# Keyboard_CN.net
KiCad netlist of a schematic drawn in Altium Designer
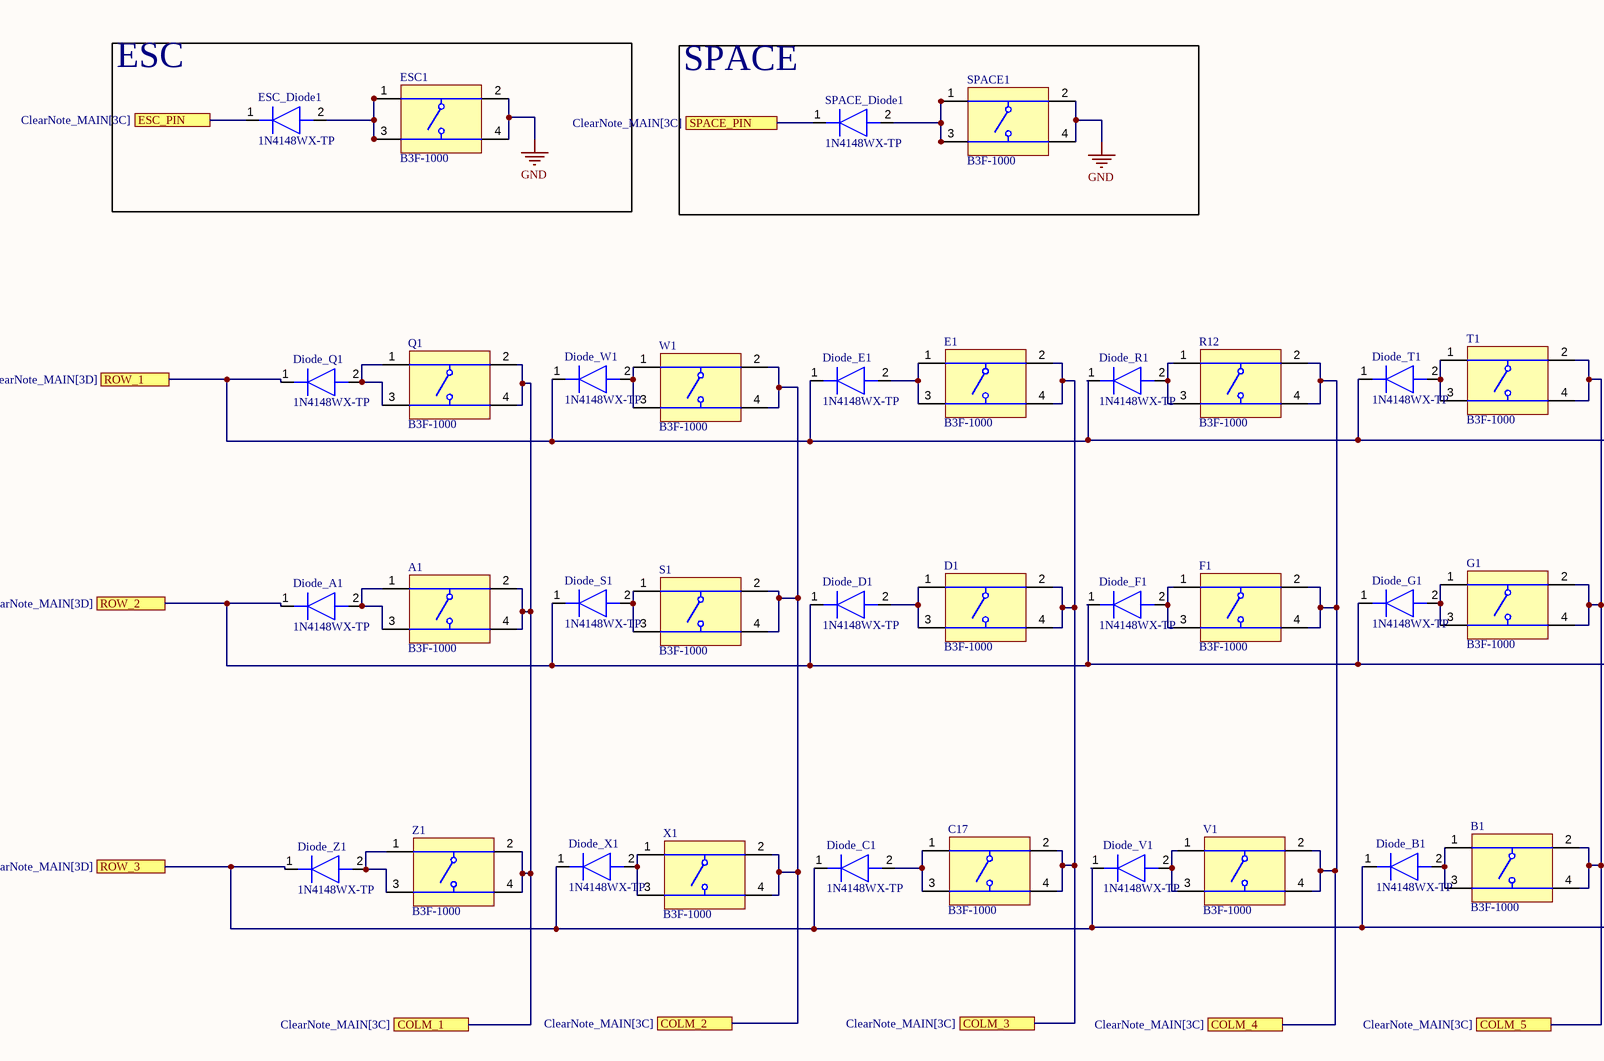
[diagram p0: Keyboard_CN.SchDoc, left]
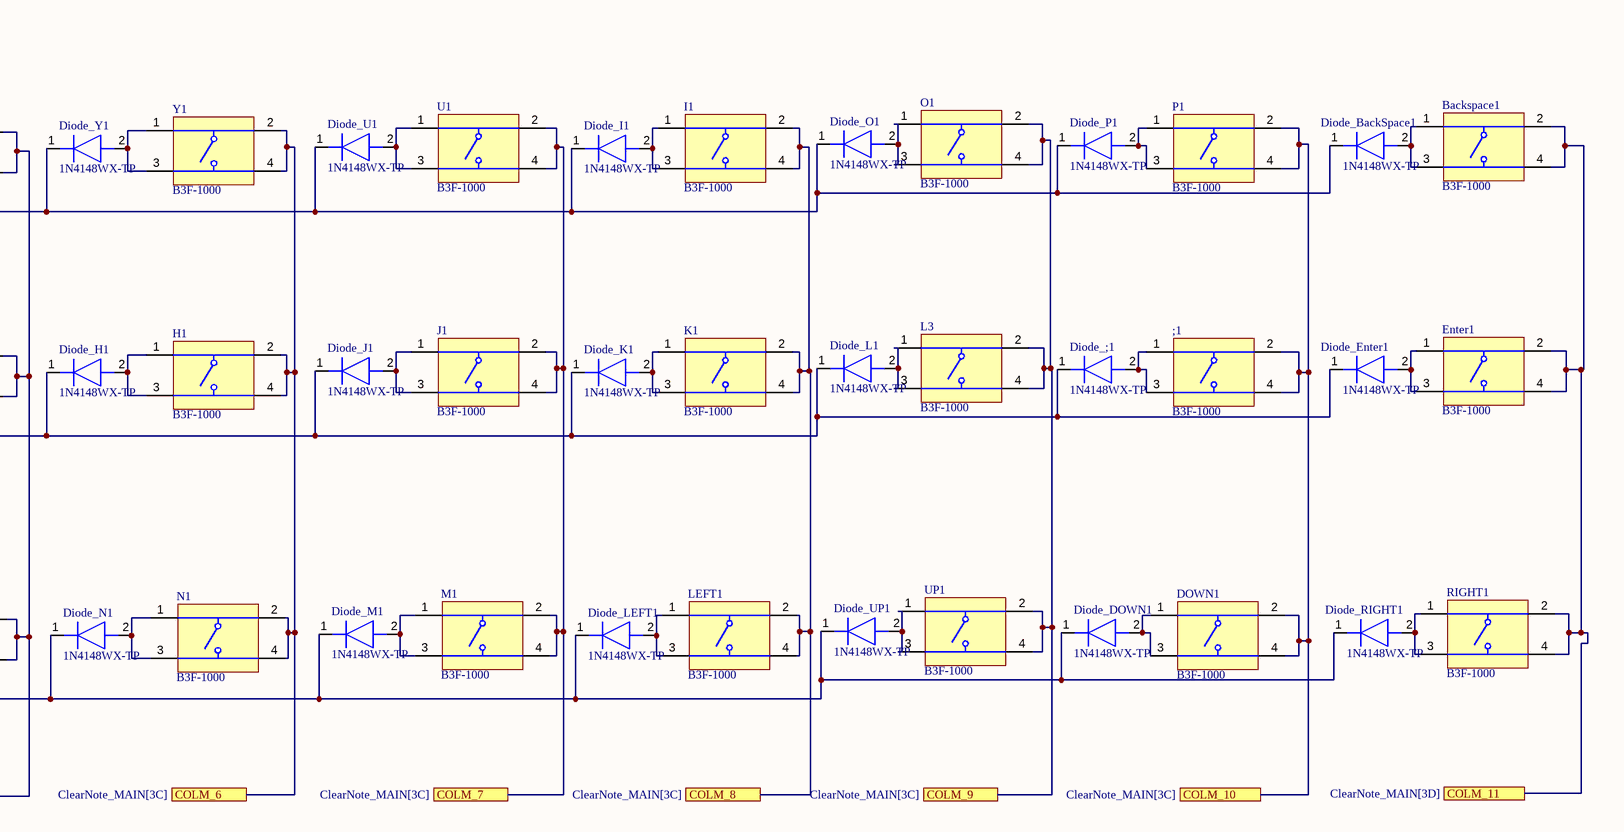
[diagram p1: Keyboard_CN.SchDoc, right]

(export (version "E")
  (design (tool "Eeschema 10.0.6"))
  (components
    (comp (ref ";1")
      (value "B3F-1000")
      (footprint "OMRON-B3F-1000-4_V")
      (description "Tactile Switch, SPST-NO, 0.05 A, 24 V, -25 to 70 degC, 4-Pin THD, RoHS, Bulk")
      (fields (field (name "MANUFACTURER") "Omron Electronic Components"))
      (libsource (lib "CAN") (part "SW-SPST-4_A"))
    )
    (comp (ref "A1")
      (value "B3F-1000")
      (footprint "OMRON-B3F-1000-4_V")
      (description "Tactile Switch, SPST-NO, 0.05 A, 24 V, -25 to 70 degC, 4-Pin THD, RoHS, Bulk")
      (fields (field (name "MANUFACTURER") "Omron Electronic Components"))
      (libsource (lib "CAN") (part "SW-SPST-4_A"))
    )
    (comp (ref "B1")
      (value "B3F-1000")
      (footprint "OMRON-B3F-1000-4_V")
      (description "Tactile Switch, SPST-NO, 0.05 A, 24 V, -25 to 70 degC, 4-Pin THD, RoHS, Bulk")
      (fields (field (name "MANUFACTURER") "Omron Electronic Components"))
      (libsource (lib "CAN") (part "SW-SPST-4_A"))
    )
    (comp (ref "Backspace1")
      (value "B3F-1000")
      (footprint "OMRON-B3F-1000-4_V")
      (description "Tactile Switch, SPST-NO, 0.05 A, 24 V, -25 to 70 degC, 4-Pin THD, RoHS, Bulk")
      (fields (field (name "MANUFACTURER") "Omron Electronic Components"))
      (libsource (lib "CAN") (part "SW-SPST-4_A"))
    )
    (comp (ref "C17")
      (value "B3F-1000")
      (footprint "OMRON-B3F-1000-4_V")
      (description "Tactile Switch, SPST-NO, 0.05 A, 24 V, -25 to 70 degC, 4-Pin THD, RoHS, Bulk")
      (fields (field (name "MANUFACTURER") "Omron Electronic Components"))
      (libsource (lib "CAN") (part "SW-SPST-4_A"))
    )
    (comp (ref "D1")
      (value "B3F-1000")
      (footprint "OMRON-B3F-1000-4_V")
      (description "Tactile Switch, SPST-NO, 0.05 A, 24 V, -25 to 70 degC, 4-Pin THD, RoHS, Bulk")
      (fields (field (name "MANUFACTURER") "Omron Electronic Components"))
      (libsource (lib "CAN") (part "SW-SPST-4_A"))
    )
    (comp (ref "Diode_;1")
      (value "1N4148WX-TP")
      (footprint "SamacSys:SOD2512X130N")
      (description "Diode")
      (libsource (lib "*") (part "1N4148WX-TP"))
    )
    (comp (ref "Diode_A1")
      (value "1N4148WX-TP")
      (footprint "SamacSys:SOD2512X130N")
      (description "Diode")
      (libsource (lib "*") (part "1N4148WX-TP"))
    )
    (comp (ref "Diode_B1")
      (value "1N4148WX-TP")
      (footprint "SamacSys:SOD2512X130N")
      (description "Diode")
      (libsource (lib "*") (part "1N4148WX-TP"))
    )
    (comp (ref "Diode_BackSpace1")
      (value "1N4148WX-TP")
      (footprint "SamacSys:SOD2512X130N")
      (description "Diode")
      (libsource (lib "*") (part "1N4148WX-TP"))
    )
    (comp (ref "Diode_C1")
      (value "1N4148WX-TP")
      (footprint "SamacSys:SOD2512X130N")
      (description "Diode")
      (libsource (lib "*") (part "1N4148WX-TP"))
    )
    (comp (ref "Diode_D1")
      (value "1N4148WX-TP")
      (footprint "SamacSys:SOD2512X130N")
      (description "Diode")
      (libsource (lib "*") (part "1N4148WX-TP"))
    )
    (comp (ref "Diode_DOWN1")
      (value "1N4148WX-TP")
      (footprint "SamacSys:SOD2512X130N")
      (description "Diode")
      (libsource (lib "*") (part "1N4148WX-TP"))
    )
    (comp (ref "Diode_E1")
      (value "1N4148WX-TP")
      (footprint "SamacSys:SOD2512X130N")
      (description "Diode")
      (libsource (lib "*") (part "1N4148WX-TP"))
    )
    (comp (ref "Diode_Enter1")
      (value "1N4148WX-TP")
      (footprint "SamacSys:SOD2512X130N")
      (description "Diode")
      (libsource (lib "*") (part "1N4148WX-TP"))
    )
    (comp (ref "Diode_F1")
      (value "1N4148WX-TP")
      (footprint "SamacSys:SOD2512X130N")
      (description "Diode")
      (libsource (lib "*") (part "1N4148WX-TP"))
    )
    (comp (ref "Diode_G1")
      (value "1N4148WX-TP")
      (footprint "SamacSys:SOD2512X130N")
      (description "Diode")
      (libsource (lib "*") (part "1N4148WX-TP"))
    )
    (comp (ref "Diode_H1")
      (value "1N4148WX-TP")
      (footprint "SamacSys:SOD2512X130N")
      (description "Diode")
      (libsource (lib "*") (part "1N4148WX-TP"))
    )
    (comp (ref "Diode_I1")
      (value "1N4148WX-TP")
      (footprint "SamacSys:SOD2512X130N")
      (description "Diode")
      (libsource (lib "*") (part "1N4148WX-TP"))
    )
    (comp (ref "Diode_J1")
      (value "1N4148WX-TP")
      (footprint "SamacSys:SOD2512X130N")
      (description "Diode")
      (libsource (lib "*") (part "1N4148WX-TP"))
    )
    (comp (ref "Diode_K1")
      (value "1N4148WX-TP")
      (footprint "SamacSys:SOD2512X130N")
      (description "Diode")
      (libsource (lib "*") (part "1N4148WX-TP"))
    )
    (comp (ref "Diode_L1")
      (value "1N4148WX-TP")
      (footprint "SamacSys:SOD2512X130N")
      (description "Diode")
      (libsource (lib "*") (part "1N4148WX-TP"))
    )
    (comp (ref "Diode_LEFT1")
      (value "1N4148WX-TP")
      (footprint "SamacSys:SOD2512X130N")
      (description "Diode")
      (libsource (lib "*") (part "1N4148WX-TP"))
    )
    (comp (ref "Diode_M1")
      (value "1N4148WX-TP")
      (footprint "SamacSys:SOD2512X130N")
      (description "Diode")
      (libsource (lib "*") (part "1N4148WX-TP"))
    )
    (comp (ref "Diode_N1")
      (value "1N4148WX-TP")
      (footprint "SamacSys:SOD2512X130N")
      (description "Diode")
      (libsource (lib "*") (part "1N4148WX-TP"))
    )
    (comp (ref "Diode_O1")
      (value "1N4148WX-TP")
      (footprint "SamacSys:SOD2512X130N")
      (description "Diode")
      (libsource (lib "*") (part "1N4148WX-TP"))
    )
    (comp (ref "Diode_P1")
      (value "1N4148WX-TP")
      (footprint "SamacSys:SOD2512X130N")
      (description "Diode")
      (libsource (lib "*") (part "1N4148WX-TP"))
    )
    (comp (ref "Diode_Q1")
      (value "1N4148WX-TP")
      (footprint "SamacSys:SOD2512X130N")
      (description "Diode")
      (libsource (lib "*") (part "1N4148WX-TP"))
    )
    (comp (ref "Diode_R1")
      (value "1N4148WX-TP")
      (footprint "SamacSys:SOD2512X130N")
      (description "Diode")
      (libsource (lib "*") (part "1N4148WX-TP"))
    )
    (comp (ref "Diode_RIGHT1")
      (value "1N4148WX-TP")
      (footprint "SamacSys:SOD2512X130N")
      (description "Diode")
      (libsource (lib "*") (part "1N4148WX-TP"))
    )
    (comp (ref "Diode_S1")
      (value "1N4148WX-TP")
      (footprint "SamacSys:SOD2512X130N")
      (description "Diode")
      (libsource (lib "*") (part "1N4148WX-TP"))
    )
    (comp (ref "Diode_T1")
      (value "1N4148WX-TP")
      (footprint "SamacSys:SOD2512X130N")
      (description "Diode")
      (libsource (lib "*") (part "1N4148WX-TP"))
    )
    (comp (ref "Diode_U1")
      (value "1N4148WX-TP")
      (footprint "SamacSys:SOD2512X130N")
      (description "Diode")
      (libsource (lib "*") (part "1N4148WX-TP"))
    )
    (comp (ref "Diode_UP1")
      (value "1N4148WX-TP")
      (footprint "SamacSys:SOD2512X130N")
      (description "Diode")
      (libsource (lib "*") (part "1N4148WX-TP"))
    )
    (comp (ref "Diode_V1")
      (value "1N4148WX-TP")
      (footprint "SamacSys:SOD2512X130N")
      (description "Diode")
      (libsource (lib "*") (part "1N4148WX-TP"))
    )
    (comp (ref "Diode_W1")
      (value "1N4148WX-TP")
      (footprint "SamacSys:SOD2512X130N")
      (description "Diode")
      (libsource (lib "*") (part "1N4148WX-TP"))
    )
    (comp (ref "Diode_X1")
      (value "1N4148WX-TP")
      (footprint "SamacSys:SOD2512X130N")
      (description "Diode")
      (libsource (lib "*") (part "1N4148WX-TP"))
    )
    (comp (ref "Diode_Y1")
      (value "1N4148WX-TP")
      (footprint "SamacSys:SOD2512X130N")
      (description "Diode")
      (libsource (lib "*") (part "1N4148WX-TP"))
    )
    (comp (ref "Diode_Z1")
      (value "1N4148WX-TP")
      (footprint "SamacSys:SOD2512X130N")
      (description "Diode")
      (libsource (lib "*") (part "1N4148WX-TP"))
    )
    (comp (ref "DOWN1")
      (value "B3F-1000")
      (footprint "OMRON-B3F-1000-4_V")
      (description "Tactile Switch, SPST-NO, 0.05 A, 24 V, -25 to 70 degC, 4-Pin THD, RoHS, Bulk")
      (fields (field (name "MANUFACTURER") "Omron Electronic Components"))
      (libsource (lib "CAN") (part "SW-SPST-4_A"))
    )
    (comp (ref "E1")
      (value "B3F-1000")
      (footprint "OMRON-B3F-1000-4_V")
      (description "Tactile Switch, SPST-NO, 0.05 A, 24 V, -25 to 70 degC, 4-Pin THD, RoHS, Bulk")
      (fields (field (name "MANUFACTURER") "Omron Electronic Components"))
      (libsource (lib "CAN") (part "SW-SPST-4_A"))
    )
    (comp (ref "Enter1")
      (value "B3F-1000")
      (footprint "OMRON-B3F-1000-4_V")
      (description "Tactile Switch, SPST-NO, 0.05 A, 24 V, -25 to 70 degC, 4-Pin THD, RoHS, Bulk")
      (fields (field (name "MANUFACTURER") "Omron Electronic Components"))
      (libsource (lib "CAN") (part "SW-SPST-4_A"))
    )
    (comp (ref "ESC1")
      (value "B3F-1000")
      (footprint "OMRON-B3F-1000-4_V")
      (description "Tactile Switch, SPST-NO, 0.05 A, 24 V, -25 to 70 degC, 4-Pin THD, RoHS, Bulk")
      (fields (field (name "MANUFACTURER") "Omron Electronic Components"))
      (libsource (lib "CAN") (part "SW-SPST-4_A"))
    )
    (comp (ref "ESC_Diode1")
      (value "1N4148WX-TP")
      (footprint "SamacSys:SOD2512X130N")
      (description "Diode")
      (libsource (lib "*") (part "1N4148WX-TP"))
    )
    (comp (ref "F1")
      (value "B3F-1000")
      (footprint "OMRON-B3F-1000-4_V")
      (description "Tactile Switch, SPST-NO, 0.05 A, 24 V, -25 to 70 degC, 4-Pin THD, RoHS, Bulk")
      (fields (field (name "MANUFACTURER") "Omron Electronic Components"))
      (libsource (lib "CAN") (part "SW-SPST-4_A"))
    )
    (comp (ref "G1")
      (value "B3F-1000")
      (footprint "OMRON-B3F-1000-4_V")
      (description "Tactile Switch, SPST-NO, 0.05 A, 24 V, -25 to 70 degC, 4-Pin THD, RoHS, Bulk")
      (fields (field (name "MANUFACTURER") "Omron Electronic Components"))
      (libsource (lib "CAN") (part "SW-SPST-4_A"))
    )
    (comp (ref "H1")
      (value "B3F-1000")
      (footprint "OMRON-B3F-1000-4_V")
      (description "Tactile Switch, SPST-NO, 0.05 A, 24 V, -25 to 70 degC, 4-Pin THD, RoHS, Bulk")
      (fields (field (name "MANUFACTURER") "Omron Electronic Components"))
      (libsource (lib "CAN") (part "SW-SPST-4_A"))
    )
    (comp (ref "I1")
      (value "B3F-1000")
      (footprint "OMRON-B3F-1000-4_V")
      (description "Tactile Switch, SPST-NO, 0.05 A, 24 V, -25 to 70 degC, 4-Pin THD, RoHS, Bulk")
      (fields (field (name "MANUFACTURER") "Omron Electronic Components"))
      (libsource (lib "CAN") (part "SW-SPST-4_A"))
    )
    (comp (ref "J1")
      (value "B3F-1000")
      (footprint "OMRON-B3F-1000-4_V")
      (description "Tactile Switch, SPST-NO, 0.05 A, 24 V, -25 to 70 degC, 4-Pin THD, RoHS, Bulk")
      (fields (field (name "MANUFACTURER") "Omron Electronic Components"))
      (libsource (lib "CAN") (part "SW-SPST-4_A"))
    )
    (comp (ref "K1")
      (value "B3F-1000")
      (footprint "OMRON-B3F-1000-4_V")
      (description "Tactile Switch, SPST-NO, 0.05 A, 24 V, -25 to 70 degC, 4-Pin THD, RoHS, Bulk")
      (fields (field (name "MANUFACTURER") "Omron Electronic Components"))
      (libsource (lib "CAN") (part "SW-SPST-4_A"))
    )
    (comp (ref "L3")
      (value "B3F-1000")
      (footprint "OMRON-B3F-1000-4_V")
      (description "Tactile Switch, SPST-NO, 0.05 A, 24 V, -25 to 70 degC, 4-Pin THD, RoHS, Bulk")
      (fields (field (name "MANUFACTURER") "Omron Electronic Components"))
      (libsource (lib "CAN") (part "SW-SPST-4_A"))
    )
    (comp (ref "LEFT1")
      (value "B3F-1000")
      (footprint "OMRON-B3F-1000-4_V")
      (description "Tactile Switch, SPST-NO, 0.05 A, 24 V, -25 to 70 degC, 4-Pin THD, RoHS, Bulk")
      (fields (field (name "MANUFACTURER") "Omron Electronic Components"))
      (libsource (lib "CAN") (part "SW-SPST-4_A"))
    )
    (comp (ref "M1")
      (value "B3F-1000")
      (footprint "OMRON-B3F-1000-4_V")
      (description "Tactile Switch, SPST-NO, 0.05 A, 24 V, -25 to 70 degC, 4-Pin THD, RoHS, Bulk")
      (fields (field (name "MANUFACTURER") "Omron Electronic Components"))
      (libsource (lib "CAN") (part "SW-SPST-4_A"))
    )
    (comp (ref "N1")
      (value "B3F-1000")
      (footprint "OMRON-B3F-1000-4_V")
      (description "Tactile Switch, SPST-NO, 0.05 A, 24 V, -25 to 70 degC, 4-Pin THD, RoHS, Bulk")
      (fields (field (name "MANUFACTURER") "Omron Electronic Components"))
      (libsource (lib "CAN") (part "SW-SPST-4_A"))
    )
    (comp (ref "O1")
      (value "B3F-1000")
      (footprint "OMRON-B3F-1000-4_V")
      (description "Tactile Switch, SPST-NO, 0.05 A, 24 V, -25 to 70 degC, 4-Pin THD, RoHS, Bulk")
      (fields (field (name "MANUFACTURER") "Omron Electronic Components"))
      (libsource (lib "CAN") (part "SW-SPST-4_A"))
    )
    (comp (ref "P1")
      (value "B3F-1000")
      (footprint "OMRON-B3F-1000-4_V")
      (description "Tactile Switch, SPST-NO, 0.05 A, 24 V, -25 to 70 degC, 4-Pin THD, RoHS, Bulk")
      (fields (field (name "MANUFACTURER") "Omron Electronic Components"))
      (libsource (lib "CAN") (part "SW-SPST-4_A"))
    )
    (comp (ref "Q1")
      (value "B3F-1000")
      (footprint "OMRON-B3F-1000-4_V")
      (description "Tactile Switch, SPST-NO, 0.05 A, 24 V, -25 to 70 degC, 4-Pin THD, RoHS, Bulk")
      (fields (field (name "MANUFACTURER") "Omron Electronic Components"))
      (libsource (lib "CAN") (part "SW-SPST-4_A"))
    )
    (comp (ref "R12")
      (value "B3F-1000")
      (footprint "OMRON-B3F-1000-4_V")
      (description "Tactile Switch, SPST-NO, 0.05 A, 24 V, -25 to 70 degC, 4-Pin THD, RoHS, Bulk")
      (fields (field (name "MANUFACTURER") "Omron Electronic Components"))
      (libsource (lib "CAN") (part "SW-SPST-4_A"))
    )
    (comp (ref "RIGHT1")
      (value "B3F-1000")
      (footprint "OMRON-B3F-1000-4_V")
      (description "Tactile Switch, SPST-NO, 0.05 A, 24 V, -25 to 70 degC, 4-Pin THD, RoHS, Bulk")
      (fields (field (name "MANUFACTURER") "Omron Electronic Components"))
      (libsource (lib "CAN") (part "SW-SPST-4_A"))
    )
    (comp (ref "S1")
      (value "B3F-1000")
      (footprint "OMRON-B3F-1000-4_V")
      (description "Tactile Switch, SPST-NO, 0.05 A, 24 V, -25 to 70 degC, 4-Pin THD, RoHS, Bulk")
      (fields (field (name "MANUFACTURER") "Omron Electronic Components"))
      (libsource (lib "CAN") (part "SW-SPST-4_A"))
    )
    (comp (ref "SPACE1")
      (value "B3F-1000")
      (footprint "OMRON-B3F-1000-4_V")
      (description "Tactile Switch, SPST-NO, 0.05 A, 24 V, -25 to 70 degC, 4-Pin THD, RoHS, Bulk")
      (fields (field (name "MANUFACTURER") "Omron Electronic Components"))
      (libsource (lib "CAN") (part "SW-SPST-4_A"))
    )
    (comp (ref "SPACE_Diode1")
      (value "1N4148WX-TP")
      (footprint "SamacSys:SOD2512X130N")
      (description "Diode")
      (libsource (lib "*") (part "1N4148WX-TP"))
    )
    (comp (ref "T1")
      (value "B3F-1000")
      (footprint "OMRON-B3F-1000-4_V")
      (description "Tactile Switch, SPST-NO, 0.05 A, 24 V, -25 to 70 degC, 4-Pin THD, RoHS, Bulk")
      (fields (field (name "MANUFACTURER") "Omron Electronic Components"))
      (libsource (lib "CAN") (part "SW-SPST-4_A"))
    )
    (comp (ref "U1")
      (value "B3F-1000")
      (footprint "OMRON-B3F-1000-4_V")
      (description "Tactile Switch, SPST-NO, 0.05 A, 24 V, -25 to 70 degC, 4-Pin THD, RoHS, Bulk")
      (fields (field (name "MANUFACTURER") "Omron Electronic Components"))
      (libsource (lib "CAN") (part "SW-SPST-4_A"))
    )
    (comp (ref "UP1")
      (value "B3F-1000")
      (footprint "OMRON-B3F-1000-4_V")
      (description "Tactile Switch, SPST-NO, 0.05 A, 24 V, -25 to 70 degC, 4-Pin THD, RoHS, Bulk")
      (fields (field (name "MANUFACTURER") "Omron Electronic Components"))
      (libsource (lib "CAN") (part "SW-SPST-4_A"))
    )
    (comp (ref "V1")
      (value "B3F-1000")
      (footprint "OMRON-B3F-1000-4_V")
      (description "Tactile Switch, SPST-NO, 0.05 A, 24 V, -25 to 70 degC, 4-Pin THD, RoHS, Bulk")
      (fields (field (name "MANUFACTURER") "Omron Electronic Components"))
      (libsource (lib "CAN") (part "SW-SPST-4_A"))
    )
    (comp (ref "W1")
      (value "B3F-1000")
      (footprint "OMRON-B3F-1000-4_V")
      (description "Tactile Switch, SPST-NO, 0.05 A, 24 V, -25 to 70 degC, 4-Pin THD, RoHS, Bulk")
      (fields (field (name "MANUFACTURER") "Omron Electronic Components"))
      (libsource (lib "CAN") (part "SW-SPST-4_A"))
    )
    (comp (ref "X1")
      (value "B3F-1000")
      (footprint "OMRON-B3F-1000-4_V")
      (description "Tactile Switch, SPST-NO, 0.05 A, 24 V, -25 to 70 degC, 4-Pin THD, RoHS, Bulk")
      (fields (field (name "MANUFACTURER") "Omron Electronic Components"))
      (libsource (lib "CAN") (part "SW-SPST-4_A"))
    )
    (comp (ref "Y1")
      (value "B3F-1000")
      (footprint "OMRON-B3F-1000-4_V")
      (description "Tactile Switch, SPST-NO, 0.05 A, 24 V, -25 to 70 degC, 4-Pin THD, RoHS, Bulk")
      (fields (field (name "MANUFACTURER") "Omron Electronic Components"))
      (libsource (lib "CAN") (part "SW-SPST-4_A"))
    )
    (comp (ref "Z1")
      (value "B3F-1000")
      (footprint "OMRON-B3F-1000-4_V")
      (description "Tactile Switch, SPST-NO, 0.05 A, 24 V, -25 to 70 degC, 4-Pin THD, RoHS, Bulk")
      (fields (field (name "MANUFACTURER") "Omron Electronic Components"))
      (libsource (lib "CAN") (part "SW-SPST-4_A"))
    )
  )
  (nets
    (net (code "1") (name "/COLM_1") (class "Default")
      (node (ref "A1") (pin "2") (pinfunction "2_2") (pintype "passive"))
      (node (ref "A1") (pin "4") (pinfunction "4_4") (pintype "passive"))
      (node (ref "Q1") (pin "2") (pinfunction "2_2") (pintype "passive"))
      (node (ref "Q1") (pin "4") (pinfunction "4_4") (pintype "passive"))
      (node (ref "Z1") (pin "2") (pinfunction "2_2") (pintype "passive"))
      (node (ref "Z1") (pin "4") (pinfunction "4_4") (pintype "passive"))
    )
    (net (code "2") (name "/COLM_2") (class "Default")
      (node (ref "S1") (pin "2") (pinfunction "2_2") (pintype "passive"))
      (node (ref "S1") (pin "4") (pinfunction "4_4") (pintype "passive"))
      (node (ref "W1") (pin "2") (pinfunction "2_2") (pintype "passive"))
      (node (ref "W1") (pin "4") (pinfunction "4_4") (pintype "passive"))
      (node (ref "X1") (pin "2") (pinfunction "2_2") (pintype "passive"))
      (node (ref "X1") (pin "4") (pinfunction "4_4") (pintype "passive"))
    )
    (net (code "3") (name "/COLM_3") (class "Default")
      (node (ref "C17") (pin "2") (pinfunction "2_2") (pintype "passive"))
      (node (ref "C17") (pin "4") (pinfunction "4_4") (pintype "passive"))
      (node (ref "D1") (pin "2") (pinfunction "2_2") (pintype "passive"))
      (node (ref "D1") (pin "4") (pinfunction "4_4") (pintype "passive"))
      (node (ref "E1") (pin "2") (pinfunction "2_2") (pintype "passive"))
      (node (ref "E1") (pin "4") (pinfunction "4_4") (pintype "passive"))
    )
    (net (code "4") (name "/COLM_4") (class "Default")
      (node (ref "F1") (pin "2") (pinfunction "2_2") (pintype "passive"))
      (node (ref "F1") (pin "4") (pinfunction "4_4") (pintype "passive"))
      (node (ref "R12") (pin "2") (pinfunction "2_2") (pintype "passive"))
      (node (ref "R12") (pin "4") (pinfunction "4_4") (pintype "passive"))
      (node (ref "V1") (pin "2") (pinfunction "2_2") (pintype "passive"))
      (node (ref "V1") (pin "4") (pinfunction "4_4") (pintype "passive"))
    )
    (net (code "5") (name "/COLM_5") (class "Default")
      (node (ref "B1") (pin "2") (pinfunction "2_2") (pintype "passive"))
      (node (ref "B1") (pin "4") (pinfunction "4_4") (pintype "passive"))
      (node (ref "G1") (pin "2") (pinfunction "2_2") (pintype "passive"))
      (node (ref "G1") (pin "4") (pinfunction "4_4") (pintype "passive"))
      (node (ref "T1") (pin "2") (pinfunction "2_2") (pintype "passive"))
      (node (ref "T1") (pin "4") (pinfunction "4_4") (pintype "passive"))
    )
    (net (code "6") (name "/COLM_6") (class "Default")
      (node (ref "H1") (pin "2") (pinfunction "2_2") (pintype "passive"))
      (node (ref "H1") (pin "4") (pinfunction "4_4") (pintype "passive"))
      (node (ref "N1") (pin "2") (pinfunction "2_2") (pintype "passive"))
      (node (ref "N1") (pin "4") (pinfunction "4_4") (pintype "passive"))
      (node (ref "Y1") (pin "2") (pinfunction "2_2") (pintype "passive"))
      (node (ref "Y1") (pin "4") (pinfunction "4_4") (pintype "passive"))
    )
    (net (code "7") (name "/COLM_7") (class "Default")
      (node (ref "J1") (pin "2") (pinfunction "2_2") (pintype "passive"))
      (node (ref "J1") (pin "4") (pinfunction "4_4") (pintype "passive"))
      (node (ref "M1") (pin "2") (pinfunction "2_2") (pintype "passive"))
      (node (ref "M1") (pin "4") (pinfunction "4_4") (pintype "passive"))
      (node (ref "U1") (pin "2") (pinfunction "2_2") (pintype "passive"))
      (node (ref "U1") (pin "4") (pinfunction "4_4") (pintype "passive"))
    )
    (net (code "8") (name "/COLM_8") (class "Default")
      (node (ref "I1") (pin "2") (pinfunction "2_2") (pintype "passive"))
      (node (ref "I1") (pin "4") (pinfunction "4_4") (pintype "passive"))
      (node (ref "K1") (pin "2") (pinfunction "2_2") (pintype "passive"))
      (node (ref "K1") (pin "4") (pinfunction "4_4") (pintype "passive"))
      (node (ref "LEFT1") (pin "2") (pinfunction "2_2") (pintype "passive"))
      (node (ref "LEFT1") (pin "4") (pinfunction "4_4") (pintype "passive"))
    )
    (net (code "9") (name "/COLM_9") (class "Default")
      (node (ref "L3") (pin "2") (pinfunction "2_2") (pintype "passive"))
      (node (ref "L3") (pin "4") (pinfunction "4_4") (pintype "passive"))
      (node (ref "O1") (pin "2") (pinfunction "2_2") (pintype "passive"))
      (node (ref "O1") (pin "4") (pinfunction "4_4") (pintype "passive"))
      (node (ref "UP1") (pin "2") (pinfunction "2_2") (pintype "passive"))
      (node (ref "UP1") (pin "4") (pinfunction "4_4") (pintype "passive"))
    )
    (net (code "10") (name "/COLM_10") (class "Default")
      (node (ref ";1") (pin "2") (pinfunction "2_2") (pintype "passive"))
      (node (ref ";1") (pin "4") (pinfunction "4_4") (pintype "passive"))
      (node (ref "DOWN1") (pin "2") (pinfunction "2_2") (pintype "passive"))
      (node (ref "DOWN1") (pin "4") (pinfunction "4_4") (pintype "passive"))
      (node (ref "P1") (pin "2") (pinfunction "2_2") (pintype "passive"))
      (node (ref "P1") (pin "4") (pinfunction "4_4") (pintype "passive"))
    )
    (net (code "11") (name "/COLM_11") (class "Default")
      (node (ref "Backspace1") (pin "2") (pinfunction "2_2") (pintype "passive"))
      (node (ref "Backspace1") (pin "4") (pinfunction "4_4") (pintype "passive"))
      (node (ref "Enter1") (pin "2") (pinfunction "2_2") (pintype "passive"))
      (node (ref "Enter1") (pin "4") (pinfunction "4_4") (pintype "passive"))
      (node (ref "RIGHT1") (pin "2") (pinfunction "2_2") (pintype "passive"))
      (node (ref "RIGHT1") (pin "4") (pinfunction "4_4") (pintype "passive"))
    )
    (net (code "12") (name "/ESC_PIN") (class "Default")
      (node (ref "ESC_Diode1") (pin "1") (pinfunction "K_1") (pintype "passive"))
    )
    (net (code "13") (name "/ROW_1") (class "Default")
      (node (ref "Diode_BackSpace1") (pin "1") (pinfunction "K_1") (pintype "passive"))
      (node (ref "Diode_E1") (pin "1") (pinfunction "K_1") (pintype "passive"))
      (node (ref "Diode_I1") (pin "1") (pinfunction "K_1") (pintype "passive"))
      (node (ref "Diode_O1") (pin "1") (pinfunction "K_1") (pintype "passive"))
      (node (ref "Diode_P1") (pin "1") (pinfunction "K_1") (pintype "passive"))
      (node (ref "Diode_Q1") (pin "1") (pinfunction "K_1") (pintype "passive"))
      (node (ref "Diode_R1") (pin "1") (pinfunction "K_1") (pintype "passive"))
      (node (ref "Diode_T1") (pin "1") (pinfunction "K_1") (pintype "passive"))
      (node (ref "Diode_U1") (pin "1") (pinfunction "K_1") (pintype "passive"))
      (node (ref "Diode_W1") (pin "1") (pinfunction "K_1") (pintype "passive"))
      (node (ref "Diode_Y1") (pin "1") (pinfunction "K_1") (pintype "passive"))
    )
    (net (code "14") (name "/ROW_2") (class "Default")
      (node (ref "Diode_;1") (pin "1") (pinfunction "K_1") (pintype "passive"))
      (node (ref "Diode_A1") (pin "1") (pinfunction "K_1") (pintype "passive"))
      (node (ref "Diode_D1") (pin "1") (pinfunction "K_1") (pintype "passive"))
      (node (ref "Diode_Enter1") (pin "1") (pinfunction "K_1") (pintype "passive"))
      (node (ref "Diode_F1") (pin "1") (pinfunction "K_1") (pintype "passive"))
      (node (ref "Diode_G1") (pin "1") (pinfunction "K_1") (pintype "passive"))
      (node (ref "Diode_H1") (pin "1") (pinfunction "K_1") (pintype "passive"))
      (node (ref "Diode_J1") (pin "1") (pinfunction "K_1") (pintype "passive"))
      (node (ref "Diode_K1") (pin "1") (pinfunction "K_1") (pintype "passive"))
      (node (ref "Diode_L1") (pin "1") (pinfunction "K_1") (pintype "passive"))
      (node (ref "Diode_S1") (pin "1") (pinfunction "K_1") (pintype "passive"))
    )
    (net (code "15") (name "/ROW_3") (class "Default")
      (node (ref "Diode_B1") (pin "1") (pinfunction "K_1") (pintype "passive"))
      (node (ref "Diode_C1") (pin "1") (pinfunction "K_1") (pintype "passive"))
      (node (ref "Diode_DOWN1") (pin "1") (pinfunction "K_1") (pintype "passive"))
      (node (ref "Diode_LEFT1") (pin "1") (pinfunction "K_1") (pintype "passive"))
      (node (ref "Diode_M1") (pin "1") (pinfunction "K_1") (pintype "passive"))
      (node (ref "Diode_N1") (pin "1") (pinfunction "K_1") (pintype "passive"))
      (node (ref "Diode_RIGHT1") (pin "1") (pinfunction "K_1") (pintype "passive"))
      (node (ref "Diode_UP1") (pin "1") (pinfunction "K_1") (pintype "passive"))
      (node (ref "Diode_V1") (pin "1") (pinfunction "K_1") (pintype "passive"))
      (node (ref "Diode_X1") (pin "1") (pinfunction "K_1") (pintype "passive"))
      (node (ref "Diode_Z1") (pin "1") (pinfunction "K_1") (pintype "passive"))
    )
    (net (code "16") (name "/SPACE_PIN") (class "Default")
      (node (ref "SPACE_Diode1") (pin "1") (pinfunction "K_1") (pintype "passive"))
    )
    (net (code "17") (name "GND") (class "Default")
      (node (ref "ESC1") (pin "2") (pinfunction "2_2") (pintype "passive"))
      (node (ref "ESC1") (pin "4") (pinfunction "4_4") (pintype "passive"))
      (node (ref "SPACE1") (pin "2") (pinfunction "2_2") (pintype "passive"))
      (node (ref "SPACE1") (pin "4") (pinfunction "4_4") (pintype "passive"))
    )
    (net (code "18") (name "Net-(Diode_;1-A)") (class "Default")
      (node (ref ";1") (pin "1") (pinfunction "1_1") (pintype "passive"))
      (node (ref ";1") (pin "3") (pinfunction "3_3") (pintype "passive"))
      (node (ref "Diode_;1") (pin "2") (pinfunction "A_2") (pintype "passive"))
    )
    (net (code "19") (name "Net-(Diode_A1-A)") (class "Default")
      (node (ref "A1") (pin "1") (pinfunction "1_1") (pintype "passive"))
      (node (ref "A1") (pin "3") (pinfunction "3_3") (pintype "passive"))
      (node (ref "Diode_A1") (pin "2") (pinfunction "A_2") (pintype "passive"))
    )
    (net (code "20") (name "Net-(Diode_B1-A)") (class "Default")
      (node (ref "B1") (pin "1") (pinfunction "1_1") (pintype "passive"))
      (node (ref "B1") (pin "3") (pinfunction "3_3") (pintype "passive"))
      (node (ref "Diode_B1") (pin "2") (pinfunction "A_2") (pintype "passive"))
    )
    (net (code "21") (name "Net-(Diode_BackSpace1-A)") (class "Default")
      (node (ref "Backspace1") (pin "1") (pinfunction "1_1") (pintype "passive"))
      (node (ref "Backspace1") (pin "3") (pinfunction "3_3") (pintype "passive"))
      (node (ref "Diode_BackSpace1") (pin "2") (pinfunction "A_2") (pintype "passive"))
    )
    (net (code "22") (name "Net-(Diode_C1-A)") (class "Default")
      (node (ref "C17") (pin "1") (pinfunction "1_1") (pintype "passive"))
      (node (ref "C17") (pin "3") (pinfunction "3_3") (pintype "passive"))
      (node (ref "Diode_C1") (pin "2") (pinfunction "A_2") (pintype "passive"))
    )
    (net (code "23") (name "Net-(Diode_D1-A)") (class "Default")
      (node (ref "D1") (pin "1") (pinfunction "1_1") (pintype "passive"))
      (node (ref "D1") (pin "3") (pinfunction "3_3") (pintype "passive"))
      (node (ref "Diode_D1") (pin "2") (pinfunction "A_2") (pintype "passive"))
    )
    (net (code "24") (name "Net-(Diode_DOWN1-A)") (class "Default")
      (node (ref "DOWN1") (pin "1") (pinfunction "1_1") (pintype "passive"))
      (node (ref "DOWN1") (pin "3") (pinfunction "3_3") (pintype "passive"))
      (node (ref "Diode_DOWN1") (pin "2") (pinfunction "A_2") (pintype "passive"))
    )
    (net (code "25") (name "Net-(Diode_E1-A)") (class "Default")
      (node (ref "Diode_E1") (pin "2") (pinfunction "A_2") (pintype "passive"))
      (node (ref "E1") (pin "1") (pinfunction "1_1") (pintype "passive"))
      (node (ref "E1") (pin "3") (pinfunction "3_3") (pintype "passive"))
    )
    (net (code "26") (name "Net-(Diode_Enter1-A)") (class "Default")
      (node (ref "Diode_Enter1") (pin "2") (pinfunction "A_2") (pintype "passive"))
      (node (ref "Enter1") (pin "1") (pinfunction "1_1") (pintype "passive"))
      (node (ref "Enter1") (pin "3") (pinfunction "3_3") (pintype "passive"))
    )
    (net (code "27") (name "Net-(Diode_F1-A)") (class "Default")
      (node (ref "Diode_F1") (pin "2") (pinfunction "A_2") (pintype "passive"))
      (node (ref "F1") (pin "1") (pinfunction "1_1") (pintype "passive"))
      (node (ref "F1") (pin "3") (pinfunction "3_3") (pintype "passive"))
    )
    (net (code "28") (name "Net-(Diode_G1-A)") (class "Default")
      (node (ref "Diode_G1") (pin "2") (pinfunction "A_2") (pintype "passive"))
      (node (ref "G1") (pin "1") (pinfunction "1_1") (pintype "passive"))
      (node (ref "G1") (pin "3") (pinfunction "3_3") (pintype "passive"))
    )
    (net (code "29") (name "Net-(Diode_H1-A)") (class "Default")
      (node (ref "Diode_H1") (pin "2") (pinfunction "A_2") (pintype "passive"))
      (node (ref "H1") (pin "1") (pinfunction "1_1") (pintype "passive"))
      (node (ref "H1") (pin "3") (pinfunction "3_3") (pintype "passive"))
    )
    (net (code "30") (name "Net-(Diode_I1-A)") (class "Default")
      (node (ref "Diode_I1") (pin "2") (pinfunction "A_2") (pintype "passive"))
      (node (ref "I1") (pin "1") (pinfunction "1_1") (pintype "passive"))
      (node (ref "I1") (pin "3") (pinfunction "3_3") (pintype "passive"))
    )
    (net (code "31") (name "Net-(Diode_J1-A)") (class "Default")
      (node (ref "Diode_J1") (pin "2") (pinfunction "A_2") (pintype "passive"))
      (node (ref "J1") (pin "1") (pinfunction "1_1") (pintype "passive"))
      (node (ref "J1") (pin "3") (pinfunction "3_3") (pintype "passive"))
    )
    (net (code "32") (name "Net-(Diode_K1-A)") (class "Default")
      (node (ref "Diode_K1") (pin "2") (pinfunction "A_2") (pintype "passive"))
      (node (ref "K1") (pin "1") (pinfunction "1_1") (pintype "passive"))
      (node (ref "K1") (pin "3") (pinfunction "3_3") (pintype "passive"))
    )
    (net (code "33") (name "Net-(Diode_L1-A)") (class "Default")
      (node (ref "Diode_L1") (pin "2") (pinfunction "A_2") (pintype "passive"))
      (node (ref "L3") (pin "1") (pinfunction "1_1") (pintype "passive"))
      (node (ref "L3") (pin "3") (pinfunction "3_3") (pintype "passive"))
    )
    (net (code "34") (name "Net-(Diode_LEFT1-A)") (class "Default")
      (node (ref "Diode_LEFT1") (pin "2") (pinfunction "A_2") (pintype "passive"))
      (node (ref "LEFT1") (pin "1") (pinfunction "1_1") (pintype "passive"))
      (node (ref "LEFT1") (pin "3") (pinfunction "3_3") (pintype "passive"))
    )
    (net (code "35") (name "Net-(Diode_M1-A)") (class "Default")
      (node (ref "Diode_M1") (pin "2") (pinfunction "A_2") (pintype "passive"))
      (node (ref "M1") (pin "1") (pinfunction "1_1") (pintype "passive"))
      (node (ref "M1") (pin "3") (pinfunction "3_3") (pintype "passive"))
    )
    (net (code "36") (name "Net-(Diode_N1-A)") (class "Default")
      (node (ref "Diode_N1") (pin "2") (pinfunction "A_2") (pintype "passive"))
      (node (ref "N1") (pin "1") (pinfunction "1_1") (pintype "passive"))
      (node (ref "N1") (pin "3") (pinfunction "3_3") (pintype "passive"))
    )
    (net (code "37") (name "Net-(Diode_O1-A)") (class "Default")
      (node (ref "Diode_O1") (pin "2") (pinfunction "A_2") (pintype "passive"))
      (node (ref "O1") (pin "1") (pinfunction "1_1") (pintype "passive"))
      (node (ref "O1") (pin "3") (pinfunction "3_3") (pintype "passive"))
    )
    (net (code "38") (name "Net-(Diode_P1-A)") (class "Default")
      (node (ref "Diode_P1") (pin "2") (pinfunction "A_2") (pintype "passive"))
      (node (ref "P1") (pin "1") (pinfunction "1_1") (pintype "passive"))
      (node (ref "P1") (pin "3") (pinfunction "3_3") (pintype "passive"))
    )
    (net (code "39") (name "Net-(Diode_Q1-A)") (class "Default")
      (node (ref "Diode_Q1") (pin "2") (pinfunction "A_2") (pintype "passive"))
      (node (ref "Q1") (pin "1") (pinfunction "1_1") (pintype "passive"))
      (node (ref "Q1") (pin "3") (pinfunction "3_3") (pintype "passive"))
    )
    (net (code "40") (name "Net-(Diode_R1-A)") (class "Default")
      (node (ref "Diode_R1") (pin "2") (pinfunction "A_2") (pintype "passive"))
      (node (ref "R12") (pin "1") (pinfunction "1_1") (pintype "passive"))
      (node (ref "R12") (pin "3") (pinfunction "3_3") (pintype "passive"))
    )
    (net (code "41") (name "Net-(Diode_RIGHT1-A)") (class "Default")
      (node (ref "Diode_RIGHT1") (pin "2") (pinfunction "A_2") (pintype "passive"))
      (node (ref "RIGHT1") (pin "1") (pinfunction "1_1") (pintype "passive"))
      (node (ref "RIGHT1") (pin "3") (pinfunction "3_3") (pintype "passive"))
    )
    (net (code "42") (name "Net-(Diode_S1-A)") (class "Default")
      (node (ref "Diode_S1") (pin "2") (pinfunction "A_2") (pintype "passive"))
      (node (ref "S1") (pin "1") (pinfunction "1_1") (pintype "passive"))
      (node (ref "S1") (pin "3") (pinfunction "3_3") (pintype "passive"))
    )
    (net (code "43") (name "Net-(Diode_T1-A)") (class "Default")
      (node (ref "Diode_T1") (pin "2") (pinfunction "A_2") (pintype "passive"))
      (node (ref "T1") (pin "1") (pinfunction "1_1") (pintype "passive"))
      (node (ref "T1") (pin "3") (pinfunction "3_3") (pintype "passive"))
    )
    (net (code "44") (name "Net-(Diode_U1-A)") (class "Default")
      (node (ref "Diode_U1") (pin "2") (pinfunction "A_2") (pintype "passive"))
      (node (ref "U1") (pin "1") (pinfunction "1_1") (pintype "passive"))
      (node (ref "U1") (pin "3") (pinfunction "3_3") (pintype "passive"))
    )
    (net (code "45") (name "Net-(Diode_UP1-A)") (class "Default")
      (node (ref "Diode_UP1") (pin "2") (pinfunction "A_2") (pintype "passive"))
      (node (ref "UP1") (pin "1") (pinfunction "1_1") (pintype "passive"))
      (node (ref "UP1") (pin "3") (pinfunction "3_3") (pintype "passive"))
    )
    (net (code "46") (name "Net-(Diode_V1-A)") (class "Default")
      (node (ref "Diode_V1") (pin "2") (pinfunction "A_2") (pintype "passive"))
      (node (ref "V1") (pin "1") (pinfunction "1_1") (pintype "passive"))
      (node (ref "V1") (pin "3") (pinfunction "3_3") (pintype "passive"))
    )
    (net (code "47") (name "Net-(Diode_W1-A)") (class "Default")
      (node (ref "Diode_W1") (pin "2") (pinfunction "A_2") (pintype "passive"))
      (node (ref "W1") (pin "1") (pinfunction "1_1") (pintype "passive"))
      (node (ref "W1") (pin "3") (pinfunction "3_3") (pintype "passive"))
    )
    (net (code "48") (name "Net-(Diode_X1-A)") (class "Default")
      (node (ref "Diode_X1") (pin "2") (pinfunction "A_2") (pintype "passive"))
      (node (ref "X1") (pin "1") (pinfunction "1_1") (pintype "passive"))
      (node (ref "X1") (pin "3") (pinfunction "3_3") (pintype "passive"))
    )
    (net (code "49") (name "Net-(Diode_Y1-A)") (class "Default")
      (node (ref "Diode_Y1") (pin "2") (pinfunction "A_2") (pintype "passive"))
      (node (ref "Y1") (pin "1") (pinfunction "1_1") (pintype "passive"))
      (node (ref "Y1") (pin "3") (pinfunction "3_3") (pintype "passive"))
    )
    (net (code "50") (name "Net-(Diode_Z1-A)") (class "Default")
      (node (ref "Diode_Z1") (pin "2") (pinfunction "A_2") (pintype "passive"))
      (node (ref "Z1") (pin "1") (pinfunction "1_1") (pintype "passive"))
      (node (ref "Z1") (pin "3") (pinfunction "3_3") (pintype "passive"))
    )
    (net (code "51") (name "Net-(ESC_Diode1-A)") (class "Default")
      (node (ref "ESC1") (pin "1") (pinfunction "1_1") (pintype "passive"))
      (node (ref "ESC1") (pin "3") (pinfunction "3_3") (pintype "passive"))
      (node (ref "ESC_Diode1") (pin "2") (pinfunction "A_2") (pintype "passive"))
    )
    (net (code "52") (name "Net-(SPACE_Diode1-A)") (class "Default")
      (node (ref "SPACE1") (pin "1") (pinfunction "1_1") (pintype "passive"))
      (node (ref "SPACE1") (pin "3") (pinfunction "3_3") (pintype "passive"))
      (node (ref "SPACE_Diode1") (pin "2") (pinfunction "A_2") (pintype "passive"))
    )
  )
)
